# tweeq-extMod_DRV8830.net
KiCad netlist of a schematic drawn in EAGLE
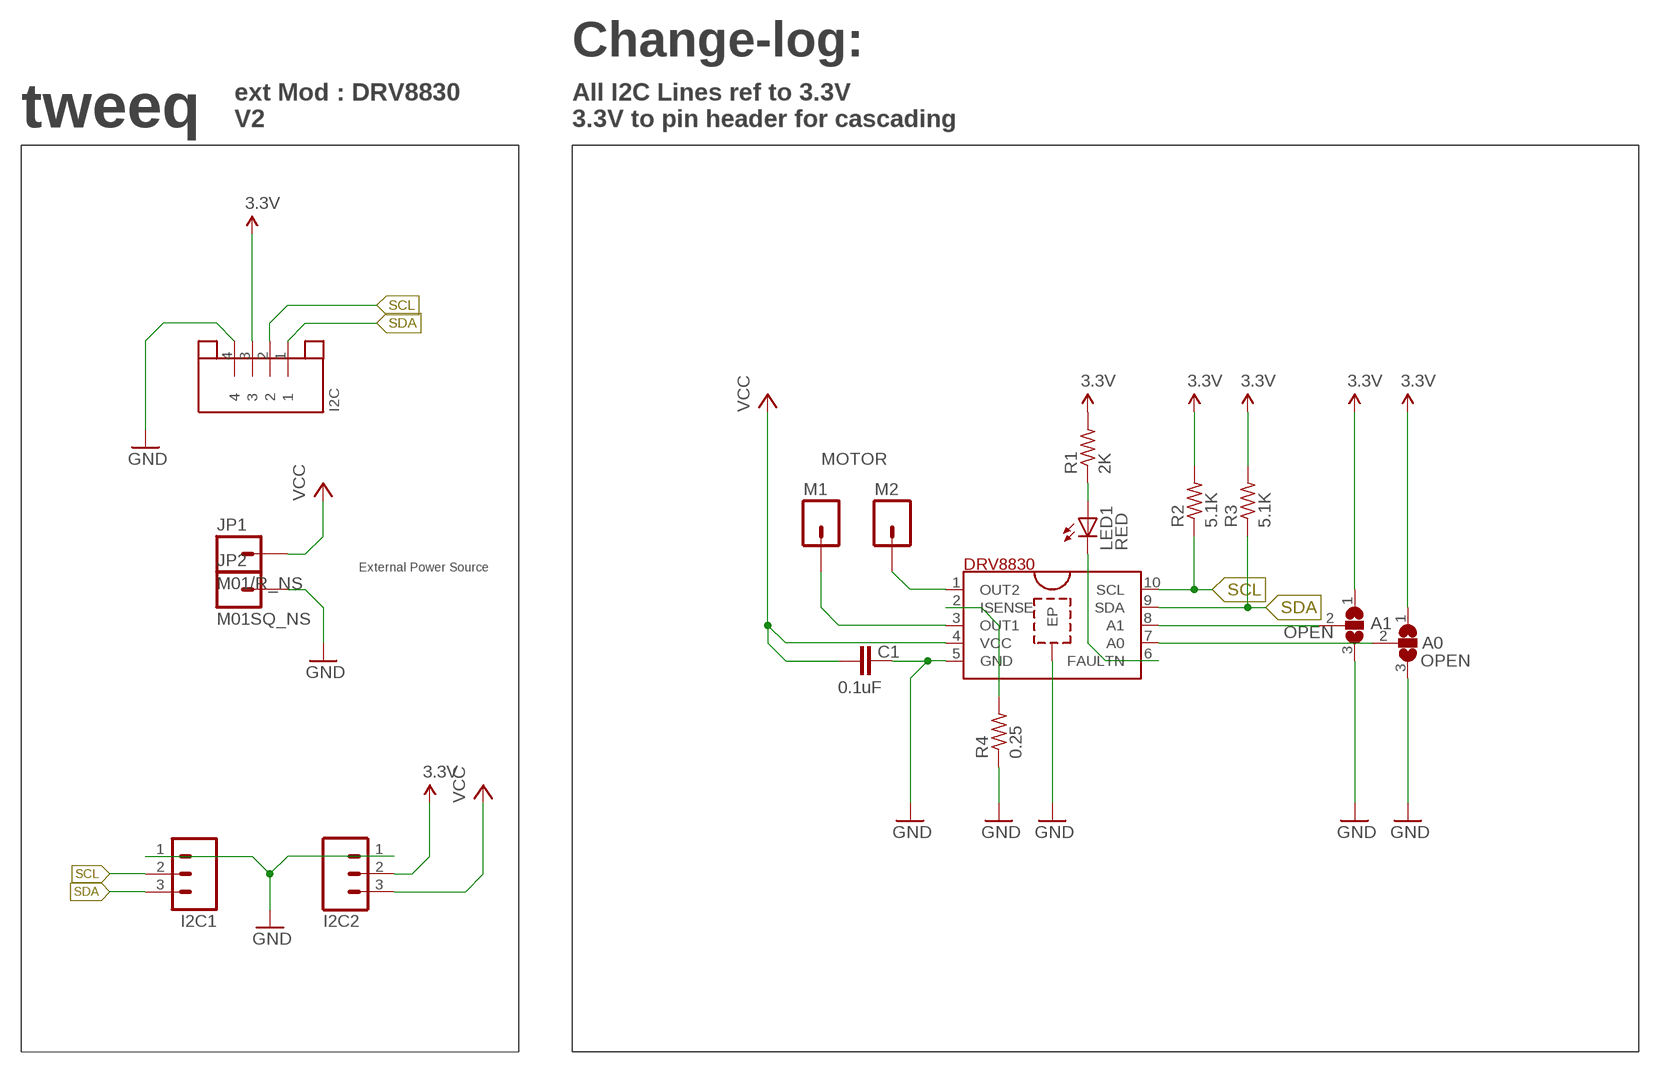
[diagram p0: schematic, sheet 1]

(export (version "E")
  (design (tool "Eeschema 10.0.6"))
  (components
    (comp (ref "A0")
      (value "OPEN")
      (footprint "eagle-import:JUMPER_SJ_S")
      (libsource (lib "eagle-import") (part "JUMPER_SJ2WS"))
    )
    (comp (ref "A1")
      (value "OPEN")
      (footprint "eagle-import:JUMPER_SJ_S")
      (libsource (lib "eagle-import") (part "JUMPER_SJ2WS"))
    )
    (comp (ref "C1")
      (value "0.1uF")
      (footprint "eagle-import:C0402K")
      (libsource (lib "eagle-import") (part "C-EUC0402K"))
    )
    (comp (ref "DRV8830")
      (value "DRV8830DGQ")
      (footprint "eagle-import:MSOP10_POWERPAD")
      (libsource (lib "eagle-import") (part "DRV8830DGQ"))
    )
    (comp (ref "I2C")
      (value "JST-4PINSH")
      (footprint "eagle-import:SH1.0-4PIN")
      (libsource (lib "eagle-import") (part "JST-4PINSH"))
    )
    (comp (ref "I2C1")
      (value "M03/NS")
      (footprint "eagle-import:1X03_NS")
      (libsource (lib "eagle-import") (part "M03/NS"))
    )
    (comp (ref "I2C2")
      (value "M03/NS")
      (footprint "eagle-import:1X03_NS")
      (libsource (lib "eagle-import") (part "M03/NS"))
    )
    (comp (ref "JP1")
      (value "M01/R_NS")
      (footprint "eagle-import:1X01NS")
      (libsource (lib "eagle-import") (part "M01/R_NS"))
    )
    (comp (ref "JP2")
      (value "M01SQ_NS")
      (footprint "eagle-import:1X01_SQ")
      (libsource (lib "eagle-import") (part "M01SQ_NS"))
    )
    (comp (ref "LED1")
      (value "RED")
      (footprint "eagle-import:CHIPLED_0805")
      (libsource (lib "eagle-import") (part "LEDCHIPLED_0805"))
    )
    (comp (ref "M1")
      (value "M01SQ_NS")
      (footprint "eagle-import:1X01_SQ")
      (libsource (lib "eagle-import") (part "M01SQ_NS"))
    )
    (comp (ref "M2")
      (value "M01SQ_NS")
      (footprint "eagle-import:1X01_SQ")
      (libsource (lib "eagle-import") (part "M01SQ_NS"))
    )
    (comp (ref "R1")
      (value "2K")
      (footprint "eagle-import:R0402")
      (libsource (lib "eagle-import") (part "R-US_R0402"))
    )
    (comp (ref "R2")
      (value "5.1K")
      (footprint "eagle-import:R0402")
      (libsource (lib "eagle-import") (part "R-US_R0402"))
    )
    (comp (ref "R3")
      (value "5.1K")
      (footprint "eagle-import:R0402")
      (libsource (lib "eagle-import") (part "R-US_R0402"))
    )
    (comp (ref "R4")
      (value "0.25")
      (footprint "eagle-import:R0402")
      (libsource (lib "eagle-import") (part "R-US_R0402"))
    )
  )
  (nets
    (net (code "1") (name "3.3V") (class "Default")
      (node (ref "A0") (pin "1") (pinfunction "1_1") (pintype "passive"))
      (node (ref "A1") (pin "1") (pinfunction "1_1") (pintype "passive"))
      (node (ref "I2C") (pin "3") (pinfunction "3_3") (pintype "bidirectional"))
      (node (ref "I2C2") (pin "2") (pinfunction "2_2") (pintype "passive"))
      (node (ref "R1") (pin "2") (pinfunction "2_2") (pintype "passive"))
      (node (ref "R2") (pin "2") (pinfunction "2_2") (pintype "passive"))
      (node (ref "R3") (pin "2") (pinfunction "2_2") (pintype "passive"))
    )
    (net (code "2") (name "GND") (class "Default")
      (node (ref "A0") (pin "3") (pinfunction "3_3") (pintype "passive"))
      (node (ref "A1") (pin "3") (pinfunction "3_3") (pintype "passive"))
      (node (ref "C1") (pin "2") (pinfunction "2_2") (pintype "passive"))
      (node (ref "DRV8830") (pin "5") (pinfunction "GND_5") (pintype "bidirectional"))
      (node (ref "DRV8830") (pin "EP") (pinfunction "EP_EP") (pintype "bidirectional"))
      (node (ref "I2C") (pin "4") (pinfunction "4_4") (pintype "bidirectional"))
      (node (ref "I2C1") (pin "1") (pinfunction "1_1") (pintype "passive"))
      (node (ref "I2C2") (pin "1") (pinfunction "1_1") (pintype "passive"))
      (node (ref "JP2") (pin "1") (pinfunction "1_1") (pintype "passive"))
      (node (ref "R4") (pin "1") (pinfunction "1_1") (pintype "passive"))
    )
    (net (code "3") (name "Net-(DRV8830-A0)") (class "Default")
      (node (ref "A0") (pin "2") (pinfunction "2_2") (pintype "passive"))
      (node (ref "DRV8830") (pin "7") (pinfunction "A0_7") (pintype "bidirectional"))
    )
    (net (code "4") (name "Net-(DRV8830-A1)") (class "Default")
      (node (ref "A1") (pin "2") (pinfunction "2_2") (pintype "passive"))
      (node (ref "DRV8830") (pin "8") (pinfunction "A1_8") (pintype "bidirectional"))
    )
    (net (code "5") (name "Net-(DRV8830-FAULTN)") (class "Default")
      (node (ref "DRV8830") (pin "6") (pinfunction "FAULTN_6") (pintype "bidirectional"))
      (node (ref "LED1") (pin "C") (pinfunction "C_C") (pintype "passive"))
    )
    (net (code "6") (name "Net-(DRV8830-ISENSE)") (class "Default")
      (node (ref "DRV8830") (pin "2") (pinfunction "ISENSE_2") (pintype "bidirectional"))
      (node (ref "R4") (pin "2") (pinfunction "2_2") (pintype "passive"))
    )
    (net (code "7") (name "Net-(DRV8830-OUT1)") (class "Default")
      (node (ref "DRV8830") (pin "3") (pinfunction "OUT1_3") (pintype "bidirectional"))
      (node (ref "M1") (pin "1") (pinfunction "1_1") (pintype "passive"))
    )
    (net (code "8") (name "Net-(DRV8830-OUT2)") (class "Default")
      (node (ref "DRV8830") (pin "1") (pinfunction "OUT2_1") (pintype "bidirectional"))
      (node (ref "M2") (pin "1") (pinfunction "1_1") (pintype "passive"))
    )
    (net (code "9") (name "Net-(LED1-PadA)") (class "Default")
      (node (ref "LED1") (pin "A") (pinfunction "A_A") (pintype "passive"))
      (node (ref "R1") (pin "1") (pinfunction "1_1") (pintype "passive"))
    )
    (net (code "10") (name "SCL") (class "Default")
      (node (ref "DRV8830") (pin "10") (pinfunction "SCL_10") (pintype "bidirectional"))
      (node (ref "I2C") (pin "2") (pinfunction "2_2") (pintype "bidirectional"))
      (node (ref "I2C1") (pin "2") (pinfunction "2_2") (pintype "passive"))
      (node (ref "R2") (pin "1") (pinfunction "1_1") (pintype "passive"))
    )
    (net (code "11") (name "SDA") (class "Default")
      (node (ref "DRV8830") (pin "9") (pinfunction "SDA_9") (pintype "bidirectional"))
      (node (ref "I2C") (pin "1") (pinfunction "1_1") (pintype "bidirectional"))
      (node (ref "I2C1") (pin "3") (pinfunction "3_3") (pintype "passive"))
      (node (ref "R3") (pin "1") (pinfunction "1_1") (pintype "passive"))
    )
    (net (code "12") (name "VCC") (class "Default")
      (node (ref "C1") (pin "1") (pinfunction "1_1") (pintype "passive"))
      (node (ref "DRV8830") (pin "4") (pinfunction "VCC_4") (pintype "bidirectional"))
      (node (ref "I2C2") (pin "3") (pinfunction "3_3") (pintype "passive"))
      (node (ref "JP1") (pin "1") (pinfunction "1_1") (pintype "passive"))
    )
  )
)
